# TTL_TO_RS485.net
KiCad netlist of a schematic drawn in Altium Designer
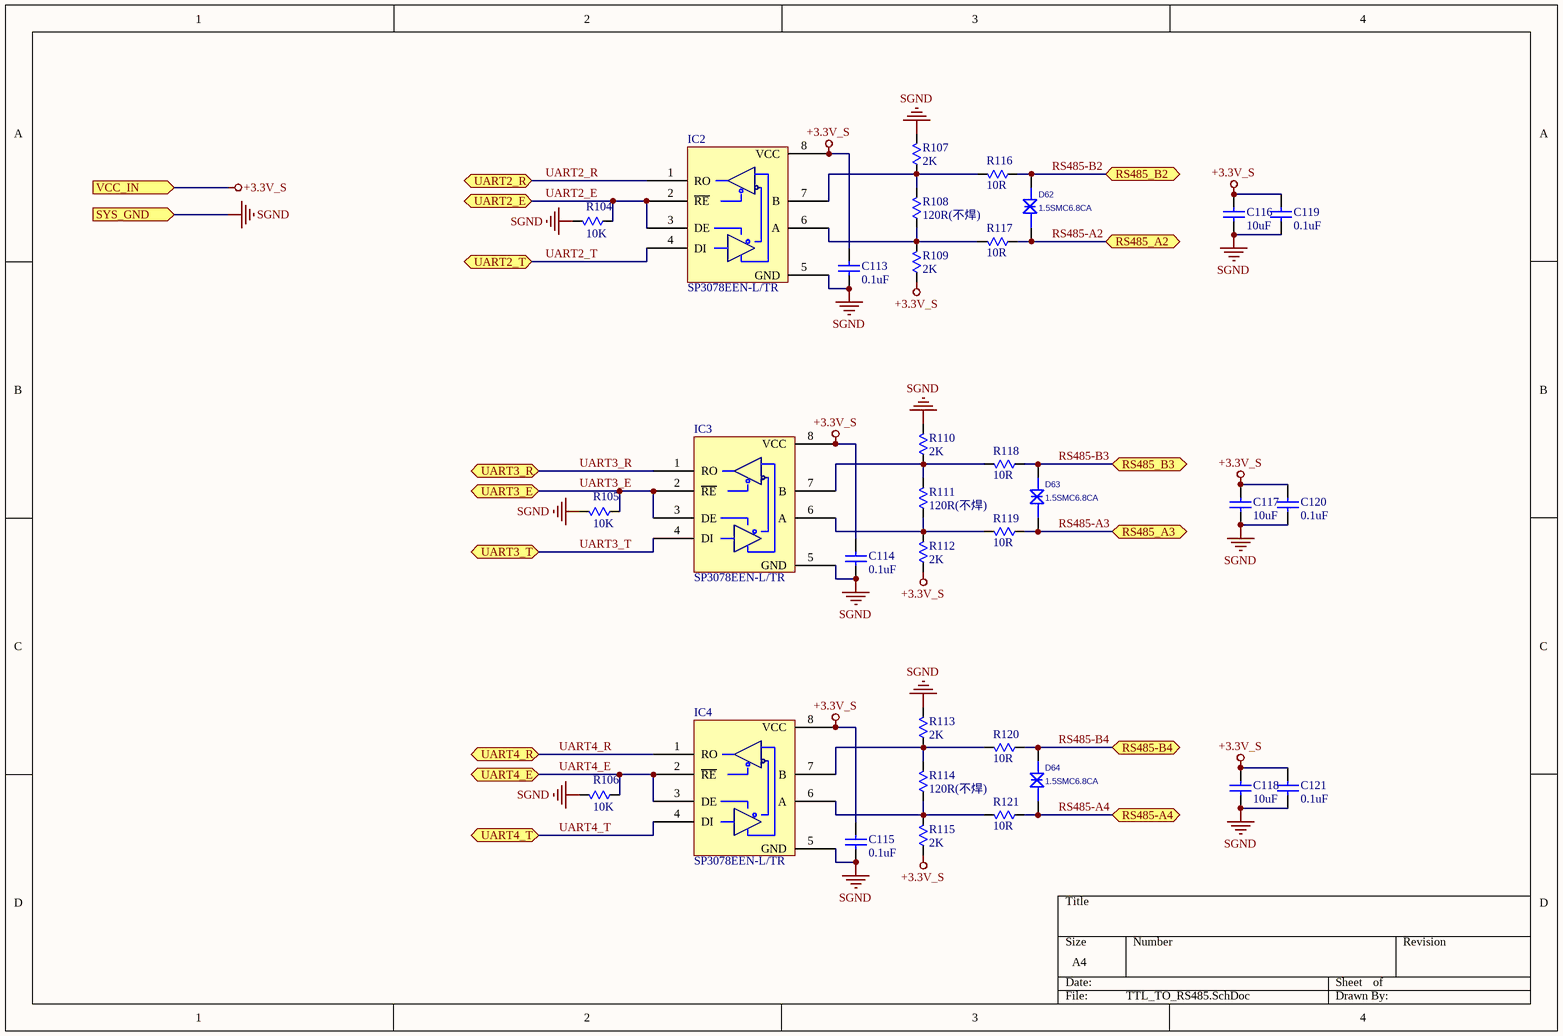
[diagram p0: TTL_TO_RS485.SchDoc]

(export (version "E")
  (design (tool "Eeschema 10.0.6"))
  (components
    (comp (ref "C113")
      (value "0.1uF")
      (footprint "C0805")
      (description "CAP")
      (fields (field (name "PUBLISHER") "Altium Limited"))
      (libsource (lib "Passive Components Class") (part "CAP"))
    )
    (comp (ref "C114")
      (value "0.1uF")
      (footprint "C0805")
      (description "CAP")
      (fields (field (name "PUBLISHER") "Altium Limited"))
      (libsource (lib "Passive Components Class") (part "CAP"))
    )
    (comp (ref "C115")
      (value "0.1uF")
      (footprint "C0805")
      (description "CAP")
      (fields (field (name "PUBLISHER") "Altium Limited"))
      (libsource (lib "Passive Components Class") (part "CAP"))
    )
    (comp (ref "C116")
      (value "10uF")
      (footprint "C1206")
      (description "CAP")
      (fields (field (name "PUBLISHER") "Altium Limited"))
      (libsource (lib "Passive Components Class") (part "CAP"))
    )
    (comp (ref "C117")
      (value "10uF")
      (footprint "C1206")
      (description "CAP")
      (fields (field (name "PUBLISHER") "Altium Limited"))
      (libsource (lib "Passive Components Class") (part "CAP"))
    )
    (comp (ref "C118")
      (value "10uF")
      (footprint "C1206")
      (description "CAP")
      (fields (field (name "PUBLISHER") "Altium Limited"))
      (libsource (lib "Passive Components Class") (part "CAP"))
    )
    (comp (ref "C119")
      (value "0.1uF")
      (footprint "C1206")
      (description "CAP")
      (fields (field (name "PUBLISHER") "Altium Limited"))
      (libsource (lib "Passive Components Class") (part "CAP"))
    )
    (comp (ref "C120")
      (value "0.1uF")
      (footprint "C1206")
      (description "CAP")
      (fields (field (name "PUBLISHER") "Altium Limited"))
      (libsource (lib "Passive Components Class") (part "CAP"))
    )
    (comp (ref "C121")
      (value "0.1uF")
      (footprint "C1206")
      (description "CAP")
      (fields (field (name "PUBLISHER") "Altium Limited"))
      (libsource (lib "Passive Components Class") (part "CAP"))
    )
    (comp (ref "D62")
      (value "1.5SMC6.8CA")
      (footprint "SMC")
      (fields (field (name "MANUFACTURER") "SemiTel"))
      (libsource (lib "*") (part "P0080_1"))
    )
    (comp (ref "D63")
      (value "1.5SMC6.8CA")
      (footprint "SMC")
      (fields (field (name "MANUFACTURER") "SemiTel"))
      (libsource (lib "*") (part "P0080_1"))
    )
    (comp (ref "D64")
      (value "1.5SMC6.8CA")
      (footprint "SMC")
      (fields (field (name "MANUFACTURER") "SemiTel"))
      (libsource (lib "*") (part "P0080_1"))
    )
    (comp (ref "IC2")
      (value "SP3078EEN-L/TR")
      (footprint "SO-8")
      (libsource (lib "Interface Class") (part "SP3078EEN"))
    )
    (comp (ref "IC3")
      (value "SP3078EEN-L/TR")
      (footprint "SO-8")
      (libsource (lib "Interface Class") (part "SP3078EEN"))
    )
    (comp (ref "IC4")
      (value "SP3078EEN-L/TR")
      (footprint "SO-8")
      (libsource (lib "Interface Class") (part "SP3078EEN"))
    )
    (comp (ref "R104")
      (value "10K")
      (footprint "R0805")
      (description "Resistor")
      (fields (field (name "PUBLISHER") "Altium Limited"))
      (libsource (lib "Passive Components Class") (part "RES"))
    )
    (comp (ref "R105")
      (value "10K")
      (footprint "R0805")
      (description "Resistor")
      (fields (field (name "PUBLISHER") "Altium Limited"))
      (libsource (lib "Passive Components Class") (part "RES"))
    )
    (comp (ref "R106")
      (value "10K")
      (footprint "R0805")
      (description "Resistor")
      (fields (field (name "PUBLISHER") "Altium Limited"))
      (libsource (lib "Passive Components Class") (part "RES"))
    )
    (comp (ref "R107")
      (value "2K")
      (footprint "R0805")
      (description "Resistor")
      (fields (field (name "PUBLISHER") "Altium Limited"))
      (libsource (lib "") (part "RES_1"))
    )
    (comp (ref "R108")
      (value "120R(不焊)")
      (footprint "R0805")
      (description "Resistor")
      (fields (field (name "PUBLISHER") "Altium Limited"))
      (libsource (lib "") (part "RES_1"))
    )
    (comp (ref "R109")
      (value "2K")
      (footprint "R0805")
      (description "Resistor")
      (fields (field (name "PUBLISHER") "Altium Limited"))
      (libsource (lib "") (part "RES_1"))
    )
    (comp (ref "R110")
      (value "2K")
      (footprint "R0805")
      (description "Resistor")
      (fields (field (name "PUBLISHER") "Altium Limited"))
      (libsource (lib "") (part "RES_1"))
    )
    (comp (ref "R111")
      (value "120R(不焊)")
      (footprint "R0805")
      (description "Resistor")
      (fields (field (name "PUBLISHER") "Altium Limited"))
      (libsource (lib "") (part "RES_1"))
    )
    (comp (ref "R112")
      (value "2K")
      (footprint "R0805")
      (description "Resistor")
      (fields (field (name "PUBLISHER") "Altium Limited"))
      (libsource (lib "") (part "RES_1"))
    )
    (comp (ref "R113")
      (value "2K")
      (footprint "R0805")
      (description "Resistor")
      (fields (field (name "PUBLISHER") "Altium Limited"))
      (libsource (lib "") (part "RES_1"))
    )
    (comp (ref "R114")
      (value "120R(不焊)")
      (footprint "R0805")
      (description "Resistor")
      (fields (field (name "PUBLISHER") "Altium Limited"))
      (libsource (lib "") (part "RES_1"))
    )
    (comp (ref "R115")
      (value "2K")
      (footprint "R0805")
      (description "Resistor")
      (fields (field (name "PUBLISHER") "Altium Limited"))
      (libsource (lib "") (part "RES_1"))
    )
    (comp (ref "R116")
      (value "10R")
      (footprint "R0805")
      (description "Resistor")
      (fields (field (name "PUBLISHER") "Altium Limited"))
      (libsource (lib "Passive Components Class") (part "RES"))
    )
    (comp (ref "R117")
      (value "10R")
      (footprint "R0805")
      (description "Resistor")
      (fields (field (name "PUBLISHER") "Altium Limited"))
      (libsource (lib "Passive Components Class") (part "RES"))
    )
    (comp (ref "R118")
      (value "10R")
      (footprint "R0805")
      (description "Resistor")
      (fields (field (name "PUBLISHER") "Altium Limited"))
      (libsource (lib "Passive Components Class") (part "RES"))
    )
    (comp (ref "R119")
      (value "10R")
      (footprint "R0805")
      (description "Resistor")
      (fields (field (name "PUBLISHER") "Altium Limited"))
      (libsource (lib "Passive Components Class") (part "RES"))
    )
    (comp (ref "R120")
      (value "10R")
      (footprint "R0805")
      (description "Resistor")
      (fields (field (name "PUBLISHER") "Altium Limited"))
      (libsource (lib "Passive Components Class") (part "RES"))
    )
    (comp (ref "R121")
      (value "10R")
      (footprint "R0805")
      (description "Resistor")
      (fields (field (name "PUBLISHER") "Altium Limited"))
      (libsource (lib "Passive Components Class") (part "RES"))
    )
  )
  (nets
    (net (code "1") (name "+3.3V_S") (class "Default")
      (node (ref "C113") (pin "2") (pinfunction "2_2") (pintype "passive"))
      (node (ref "C114") (pin "2") (pinfunction "2_2") (pintype "passive"))
      (node (ref "C115") (pin "2") (pinfunction "2_2") (pintype "passive"))
      (node (ref "C116") (pin "2") (pinfunction "2_2") (pintype "passive"))
      (node (ref "C117") (pin "2") (pinfunction "2_2") (pintype "passive"))
      (node (ref "C118") (pin "2") (pinfunction "2_2") (pintype "passive"))
      (node (ref "C119") (pin "2") (pinfunction "2_2") (pintype "passive"))
      (node (ref "C120") (pin "2") (pinfunction "2_2") (pintype "passive"))
      (node (ref "C121") (pin "2") (pinfunction "2_2") (pintype "passive"))
      (node (ref "IC2") (pin "8") (pinfunction "VCC_8") (pintype "passive"))
      (node (ref "IC3") (pin "8") (pinfunction "VCC_8") (pintype "passive"))
      (node (ref "IC4") (pin "8") (pinfunction "VCC_8") (pintype "passive"))
      (node (ref "R109") (pin "1") (pinfunction "1_1") (pintype "passive"))
      (node (ref "R112") (pin "1") (pinfunction "1_1") (pintype "passive"))
      (node (ref "R115") (pin "1") (pinfunction "1_1") (pintype "passive"))
    )
    (net (code "2") (name "/RS485-A2") (class "Default")
      (node (ref "D62") (pin "2") (pinfunction "2_2") (pintype "passive"))
      (node (ref "R117") (pin "1") (pinfunction "1_1") (pintype "passive"))
    )
    (net (code "3") (name "/RS485-A3") (class "Default")
      (node (ref "D63") (pin "2") (pinfunction "2_2") (pintype "passive"))
      (node (ref "R119") (pin "1") (pinfunction "1_1") (pintype "passive"))
    )
    (net (code "4") (name "/RS485-A4") (class "Default")
      (node (ref "D64") (pin "2") (pinfunction "2_2") (pintype "passive"))
      (node (ref "R121") (pin "1") (pinfunction "1_1") (pintype "passive"))
    )
    (net (code "5") (name "/RS485-B2") (class "Default")
      (node (ref "D62") (pin "1") (pinfunction "1_1") (pintype "passive"))
      (node (ref "R116") (pin "1") (pinfunction "1_1") (pintype "passive"))
    )
    (net (code "6") (name "/RS485-B3") (class "Default")
      (node (ref "D63") (pin "1") (pinfunction "1_1") (pintype "passive"))
      (node (ref "R118") (pin "1") (pinfunction "1_1") (pintype "passive"))
    )
    (net (code "7") (name "/RS485-B4") (class "Default")
      (node (ref "D64") (pin "1") (pinfunction "1_1") (pintype "passive"))
      (node (ref "R120") (pin "1") (pinfunction "1_1") (pintype "passive"))
    )
    (net (code "8") (name "/UART2_E") (class "Default")
      (node (ref "IC2") (pin "2") (pinfunction "~{RE}_2") (pintype "passive"))
      (node (ref "IC2") (pin "3") (pinfunction "DE_3") (pintype "passive"))
      (node (ref "R104") (pin "1") (pinfunction "1_1") (pintype "passive"))
    )
    (net (code "9") (name "/UART2_R") (class "Default")
      (node (ref "IC2") (pin "1") (pinfunction "RO_1") (pintype "passive"))
    )
    (net (code "10") (name "/UART2_T") (class "Default")
      (node (ref "IC2") (pin "4") (pinfunction "DI_4") (pintype "passive"))
    )
    (net (code "11") (name "/UART3_E") (class "Default")
      (node (ref "IC3") (pin "2") (pinfunction "~{RE}_2") (pintype "passive"))
      (node (ref "IC3") (pin "3") (pinfunction "DE_3") (pintype "passive"))
      (node (ref "R105") (pin "1") (pinfunction "1_1") (pintype "passive"))
    )
    (net (code "12") (name "/UART3_R") (class "Default")
      (node (ref "IC3") (pin "1") (pinfunction "RO_1") (pintype "passive"))
    )
    (net (code "13") (name "/UART3_T") (class "Default")
      (node (ref "IC3") (pin "4") (pinfunction "DI_4") (pintype "passive"))
    )
    (net (code "14") (name "/UART4_E") (class "Default")
      (node (ref "IC4") (pin "2") (pinfunction "~{RE}_2") (pintype "passive"))
      (node (ref "IC4") (pin "3") (pinfunction "DE_3") (pintype "passive"))
      (node (ref "R106") (pin "1") (pinfunction "1_1") (pintype "passive"))
    )
    (net (code "15") (name "/UART4_R") (class "Default")
      (node (ref "IC4") (pin "1") (pinfunction "RO_1") (pintype "passive"))
    )
    (net (code "16") (name "/UART4_T") (class "Default")
      (node (ref "IC4") (pin "4") (pinfunction "DI_4") (pintype "passive"))
    )
    (net (code "17") (name "Net-(IC2-A)") (class "Default")
      (node (ref "IC2") (pin "6") (pinfunction "A_6") (pintype "passive"))
      (node (ref "R108") (pin "1") (pinfunction "1_1") (pintype "passive"))
      (node (ref "R109") (pin "2") (pinfunction "2_2") (pintype "passive"))
      (node (ref "R117") (pin "2") (pinfunction "2_2") (pintype "passive"))
    )
    (net (code "18") (name "Net-(IC2-B)") (class "Default")
      (node (ref "IC2") (pin "7") (pinfunction "B_7") (pintype "passive"))
      (node (ref "R107") (pin "1") (pinfunction "1_1") (pintype "passive"))
      (node (ref "R108") (pin "2") (pinfunction "2_2") (pintype "passive"))
      (node (ref "R116") (pin "2") (pinfunction "2_2") (pintype "passive"))
    )
    (net (code "19") (name "Net-(IC3-A)") (class "Default")
      (node (ref "IC3") (pin "6") (pinfunction "A_6") (pintype "passive"))
      (node (ref "R111") (pin "1") (pinfunction "1_1") (pintype "passive"))
      (node (ref "R112") (pin "2") (pinfunction "2_2") (pintype "passive"))
      (node (ref "R119") (pin "2") (pinfunction "2_2") (pintype "passive"))
    )
    (net (code "20") (name "Net-(IC3-B)") (class "Default")
      (node (ref "IC3") (pin "7") (pinfunction "B_7") (pintype "passive"))
      (node (ref "R110") (pin "1") (pinfunction "1_1") (pintype "passive"))
      (node (ref "R111") (pin "2") (pinfunction "2_2") (pintype "passive"))
      (node (ref "R118") (pin "2") (pinfunction "2_2") (pintype "passive"))
    )
    (net (code "21") (name "Net-(IC4-A)") (class "Default")
      (node (ref "IC4") (pin "6") (pinfunction "A_6") (pintype "passive"))
      (node (ref "R114") (pin "1") (pinfunction "1_1") (pintype "passive"))
      (node (ref "R115") (pin "2") (pinfunction "2_2") (pintype "passive"))
      (node (ref "R121") (pin "2") (pinfunction "2_2") (pintype "passive"))
    )
    (net (code "22") (name "Net-(IC4-B)") (class "Default")
      (node (ref "IC4") (pin "7") (pinfunction "B_7") (pintype "passive"))
      (node (ref "R113") (pin "1") (pinfunction "1_1") (pintype "passive"))
      (node (ref "R114") (pin "2") (pinfunction "2_2") (pintype "passive"))
      (node (ref "R120") (pin "2") (pinfunction "2_2") (pintype "passive"))
    )
    (net (code "23") (name "SGND") (class "Default")
      (node (ref "C113") (pin "1") (pinfunction "1_1") (pintype "passive"))
      (node (ref "C114") (pin "1") (pinfunction "1_1") (pintype "passive"))
      (node (ref "C115") (pin "1") (pinfunction "1_1") (pintype "passive"))
      (node (ref "C116") (pin "1") (pinfunction "1_1") (pintype "passive"))
      (node (ref "C117") (pin "1") (pinfunction "1_1") (pintype "passive"))
      (node (ref "C118") (pin "1") (pinfunction "1_1") (pintype "passive"))
      (node (ref "C119") (pin "1") (pinfunction "1_1") (pintype "passive"))
      (node (ref "C120") (pin "1") (pinfunction "1_1") (pintype "passive"))
      (node (ref "C121") (pin "1") (pinfunction "1_1") (pintype "passive"))
      (node (ref "IC2") (pin "5") (pinfunction "GND_5") (pintype "passive"))
      (node (ref "IC3") (pin "5") (pinfunction "GND_5") (pintype "passive"))
      (node (ref "IC4") (pin "5") (pinfunction "GND_5") (pintype "passive"))
      (node (ref "R104") (pin "2") (pinfunction "2_2") (pintype "passive"))
      (node (ref "R105") (pin "2") (pinfunction "2_2") (pintype "passive"))
      (node (ref "R106") (pin "2") (pinfunction "2_2") (pintype "passive"))
      (node (ref "R107") (pin "2") (pinfunction "2_2") (pintype "passive"))
      (node (ref "R110") (pin "2") (pinfunction "2_2") (pintype "passive"))
      (node (ref "R113") (pin "2") (pinfunction "2_2") (pintype "passive"))
    )
  )
)
